# INPUT.net
KiCad netlist of a schematic drawn in Altium Designer
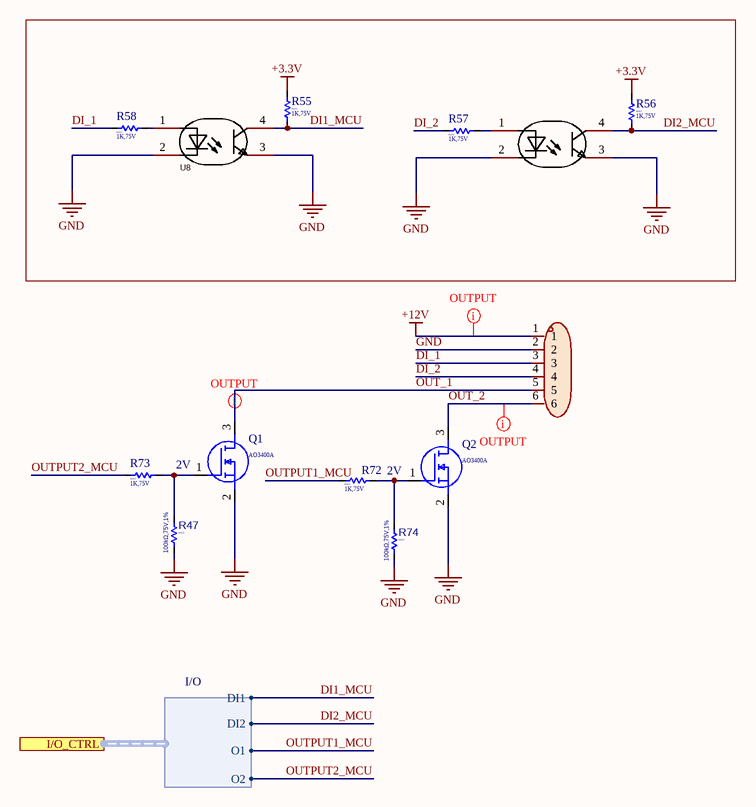
[diagram p0: INPUT.SchDoc]

(export (version "E")
  (design (tool "Eeschema 10.0.6"))
  (components
    (comp (ref "Q1")
      (value "AO3400A")
      (footprint "SOT95P280X125-3N")
      (description "MOSFET N-CH 30V 5.7A SOT23-3L")
      (fields (field (name "MANUFACTURER") "Alpha & Omega Semiconductors"))
      (libsource (lib "MOS_TRAN") (part "AO3400A"))
    )
    (comp (ref "Q2")
      (value "AO3400A")
      (footprint "SOT95P280X125-3N")
      (description "MOSFET N-CH 30V 5.7A SOT23-3L")
      (fields (field (name "MANUFACTURER") "Alpha & Omega Semiconductors"))
      (libsource (lib "MOS_TRAN") (part "AO3400A"))
    )
    (comp (ref "R47")
      (value "100kΩ,75V,1%")
      (footprint "R0603")
      (fields
        (field (name "MPN") "0603WAF1003T5E")
        (field (name "MANUFACTURER") "Royalohm")
        (field (name "PACKAGE") "0603")
        (field (name "Comment") "100K")
      )
      (libsource (lib "RCL") (part "0603WAF1003T5E"))
    )
    (comp (ref "R55")
      (value "1K,75V")
      (footprint "R0603")
      (description "100mW Thick Film Resistors 75V ±100ppm/℃ ±1% 1kΩ 0603 Chip Resistor - Surface Mount ROHS")
      (fields
        (field (name "MANUFACTURER") "UNI-ROYAL(Uniroyal Elec)")
        (field (name "MPN") "0603WAF1001T5E")
        (field (name "PACKAGE") "0603")
      )
      (libsource (lib "RCL") (part "0603WAF1001T5E"))
    )
    (comp (ref "R56")
      (value "1K,75V")
      (footprint "R0603")
      (description "100mW Thick Film Resistors 75V ±100ppm/℃ ±1% 1kΩ 0603 Chip Resistor - Surface Mount ROHS")
      (fields
        (field (name "MANUFACTURER") "UNI-ROYAL(Uniroyal Elec)")
        (field (name "MPN") "0603WAF1001T5E")
        (field (name "PACKAGE") "0603")
      )
      (libsource (lib "RCL") (part "0603WAF1001T5E"))
    )
    (comp (ref "R57")
      (value "1K,75V")
      (footprint "R0603")
      (description "100mW Thick Film Resistors 75V ±100ppm/℃ ±1% 1kΩ 0603 Chip Resistor - Surface Mount ROHS")
      (fields
        (field (name "MANUFACTURER") "UNI-ROYAL(Uniroyal Elec)")
        (field (name "MPN") "0603WAF1001T5E")
        (field (name "PACKAGE") "0603")
      )
      (libsource (lib "RCL") (part "0603WAF1001T5E"))
    )
    (comp (ref "R58")
      (value "1K,75V")
      (footprint "R0603")
      (description "100mW Thick Film Resistors 75V ±100ppm/℃ ±1% 1kΩ 0603 Chip Resistor - Surface Mount ROHS")
      (fields
        (field (name "MANUFACTURER") "UNI-ROYAL(Uniroyal Elec)")
        (field (name "MPN") "0603WAF1001T5E")
        (field (name "PACKAGE") "0603")
      )
      (libsource (lib "RCL") (part "0603WAF1001T5E"))
    )
    (comp (ref "R72")
      (value "1K,75V")
      (footprint "R0603")
      (description "100mW Thick Film Resistors 75V ±100ppm/℃ ±1% 1kΩ 0603 Chip Resistor - Surface Mount ROHS")
      (fields
        (field (name "MANUFACTURER") "UNI-ROYAL(Uniroyal Elec)")
        (field (name "MPN") "0603WAF1001T5E")
        (field (name "PACKAGE") "0603")
      )
      (libsource (lib "RCL") (part "0603WAF1001T5E"))
    )
    (comp (ref "R73")
      (value "1K,75V")
      (footprint "R0603")
      (description "100mW Thick Film Resistors 75V ±100ppm/℃ ±1% 1kΩ 0603 Chip Resistor - Surface Mount ROHS")
      (fields
        (field (name "MANUFACTURER") "UNI-ROYAL(Uniroyal Elec)")
        (field (name "MPN") "0603WAF1001T5E")
        (field (name "PACKAGE") "0603")
      )
      (libsource (lib "RCL") (part "0603WAF1001T5E"))
    )
    (comp (ref "R74")
      (value "100kΩ,75V,1%")
      (footprint "R0603")
      (fields
        (field (name "MPN") "0603WAF1003T5E")
        (field (name "MANUFACTURER") "Royalohm")
        (field (name "PACKAGE") "0603")
        (field (name "Comment") "100K")
      )
      (libsource (lib "RCL") (part "0603WAF1003T5E"))
    )
    (comp (ref "U7")
      (value "PC817X3NSZ9F")
      (footprint "DIP-4")
      (description "Optoisolator Transistor Output 5000Vrms 1 Channel 4-DIP")
      (fields (field (name "MANUFACTURER") "SHARP"))
      (libsource (lib "RCL") (part "PC817X3NSZ9F"))
    )
    (comp (ref "U8")
      (value "PC817X3NSZ9F")
      (footprint "DIP-4")
      (description "Optoisolator Transistor Output 5000Vrms 1 Channel 4-DIP")
      (fields (field (name "MANUFACTURER") "SHARP"))
      (libsource (lib "RCL") (part "PC817X3NSZ9F"))
    )
    (comp (ref "U9")
      (value "DBT50G-6.35-6P-BK-P OGC")
      (footprint "6P_P=6.35mm")
      (fields (field (name "MANUFACTURER") "DORABO(地博电气)"))
      (libsource (lib "connector_button") (part "DBT50G-6.35-6P-BK-P OGC"))
    )
  )
  (nets
    (net (code "2") (name "+3.3V") (class "Default")
      (node (ref "R55") (pin "2") (pinfunction "2_2") (pintype "passive"))
      (node (ref "R56") (pin "2") (pinfunction "2_2") (pintype "passive"))
    )
    (net (code "3") (name "+12V") (class "Default")
      (node (ref "U9") (pin "1") (pinfunction "1_1") (pintype "passive"))
    )
    (net (code "4") (name "/DI1_MCU") (class "Default")
      (node (ref "R55") (pin "1") (pinfunction "1_1") (pintype "passive"))
      (node (ref "U8") (pin "4") (pinfunction "4_4") (pintype "passive"))
    )
    (net (code "5") (name "/DI2_MCU") (class "Default")
      (node (ref "R56") (pin "1") (pinfunction "1_1") (pintype "passive"))
      (node (ref "U7") (pin "4") (pinfunction "4_4") (pintype "passive"))
    )
    (net (code "6") (name "/DI_1") (class "Default")
      (node (ref "R58") (pin "2") (pinfunction "2_2") (pintype "passive"))
      (node (ref "U9") (pin "3") (pinfunction "3_3") (pintype "passive"))
    )
    (net (code "7") (name "/DI_2") (class "Default")
      (node (ref "R57") (pin "2") (pinfunction "2_2") (pintype "passive"))
      (node (ref "U9") (pin "4") (pinfunction "4_4") (pintype "passive"))
    )
    (net (code "8") (name "/OUTPUT1_MCU") (class "Default")
      (node (ref "R72") (pin "1") (pinfunction "1_1") (pintype "passive"))
    )
    (net (code "9") (name "/OUTPUT2_MCU") (class "Default")
      (node (ref "R73") (pin "1") (pinfunction "1_1") (pintype "passive"))
    )
    (net (code "10") (name "/OUT_1") (class "Default")
      (node (ref "Q1") (pin "3") (pinfunction "D_3") (pintype "passive"))
      (node (ref "U9") (pin "5") (pinfunction "5_5") (pintype "passive"))
    )
    (net (code "11") (name "/OUT_2") (class "Default")
      (node (ref "Q2") (pin "3") (pinfunction "D_3") (pintype "passive"))
      (node (ref "U9") (pin "6") (pinfunction "6_6") (pintype "passive"))
    )
    (net (code "13") (name "GND") (class "Default")
      (node (ref "Q1") (pin "2") (pinfunction "S_2") (pintype "passive"))
      (node (ref "Q2") (pin "2") (pinfunction "S_2") (pintype "passive"))
      (node (ref "R47") (pin "1") (pinfunction "1_1") (pintype "passive"))
      (node (ref "R74") (pin "1") (pinfunction "1_1") (pintype "passive"))
      (node (ref "U7") (pin "2") (pinfunction "2_2") (pintype "passive"))
      (node (ref "U7") (pin "3") (pinfunction "3_3") (pintype "passive"))
      (node (ref "U8") (pin "2") (pinfunction "2_2") (pintype "passive"))
      (node (ref "U8") (pin "3") (pinfunction "3_3") (pintype "passive"))
      (node (ref "U9") (pin "2") (pinfunction "2_2") (pintype "passive"))
    )
    (net (code "14") (name "Net-(Q1-G)") (class "Default")
      (node (ref "Q1") (pin "1") (pinfunction "G_1") (pintype "passive"))
      (node (ref "R47") (pin "2") (pinfunction "2_2") (pintype "passive"))
      (node (ref "R73") (pin "2") (pinfunction "2_2") (pintype "passive"))
    )
    (net (code "15") (name "Net-(Q2-G)") (class "Default")
      (node (ref "Q2") (pin "1") (pinfunction "G_1") (pintype "passive"))
      (node (ref "R72") (pin "2") (pinfunction "2_2") (pintype "passive"))
      (node (ref "R74") (pin "2") (pinfunction "2_2") (pintype "passive"))
    )
    (net (code "16") (name "Net-(R57-Pad1)") (class "Default")
      (node (ref "R57") (pin "1") (pinfunction "1_1") (pintype "passive"))
      (node (ref "U7") (pin "1") (pinfunction "1_1") (pintype "passive"))
    )
    (net (code "17") (name "Net-(R58-Pad1)") (class "Default")
      (node (ref "R58") (pin "1") (pinfunction "1_1") (pintype "passive"))
      (node (ref "U8") (pin "1") (pinfunction "1_1") (pintype "passive"))
    )
  )
)
